# Viberation.net
KiCad netlist of a schematic drawn in Altium Designer
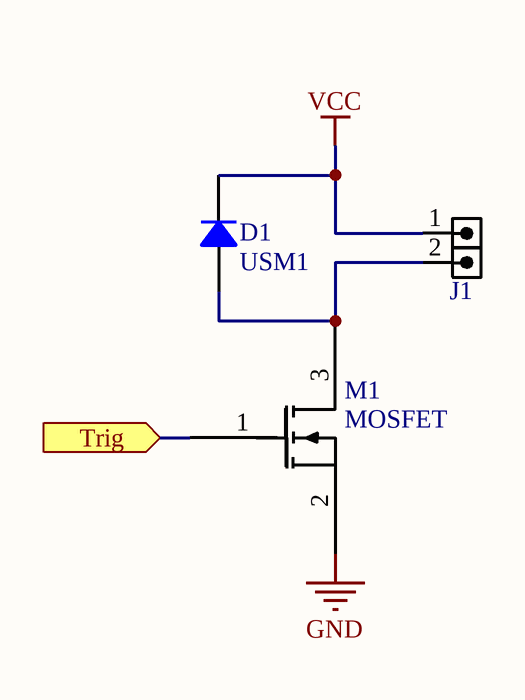
[diagram p0: Viberation.SchDoc]

(export (version "E")
  (design (tool "Eeschema 10.0.6"))
  (components
    (comp (ref "D1")
      (value "USM1")
      (footprint "DO-214AC SMA")
      (description "Diode Standard 1000V 1A Surface Mount SMA")
      (fields (field (name "PARTNUMBER") "US1M-13-F"))
      (libsource (lib "Diode") (part "US1M (SMD SMA)"))
    )
    (comp (ref "J1")
      (value "HDR2")
      (footprint "HDR1SE_M_1X2")
      (description "HEADER, 1mm pitch, test, SMD")
      (libsource (lib "Conn Header") (part "HDRTST_1X2"))
    )
    (comp (ref "M1") (value "MOSFET") (footprint "SOT-23") (libsource (lib "Salman_lib") (part "2N7002A")))
  )
  (nets
    (net (code "1") (name "/Trig") (class "Default") (node (ref "M1") (pin "1") (pintype "passive")))
    (net (code "2") (name "GND") (class "Default") (node (ref "M1") (pin "2") (pintype "passive")))
    (net (code "3") (name "Net-(D1-Pad1)") (class "Default")
      (node (ref "D1") (pin "1") (pinfunction "1_1") (pintype "passive"))
      (node (ref "J1") (pin "2") (pinfunction "2_2") (pintype "passive"))
      (node (ref "M1") (pin "3") (pintype "passive"))
    )
    (net (code "4") (name "VCC") (class "Default")
      (node (ref "D1") (pin "2") (pinfunction "2_2") (pintype "passive"))
      (node (ref "J1") (pin "1") (pinfunction "1_1") (pintype "passive"))
    )
  )
)
